# UI.net
KiCad netlist of a schematic drawn in Altium Designer
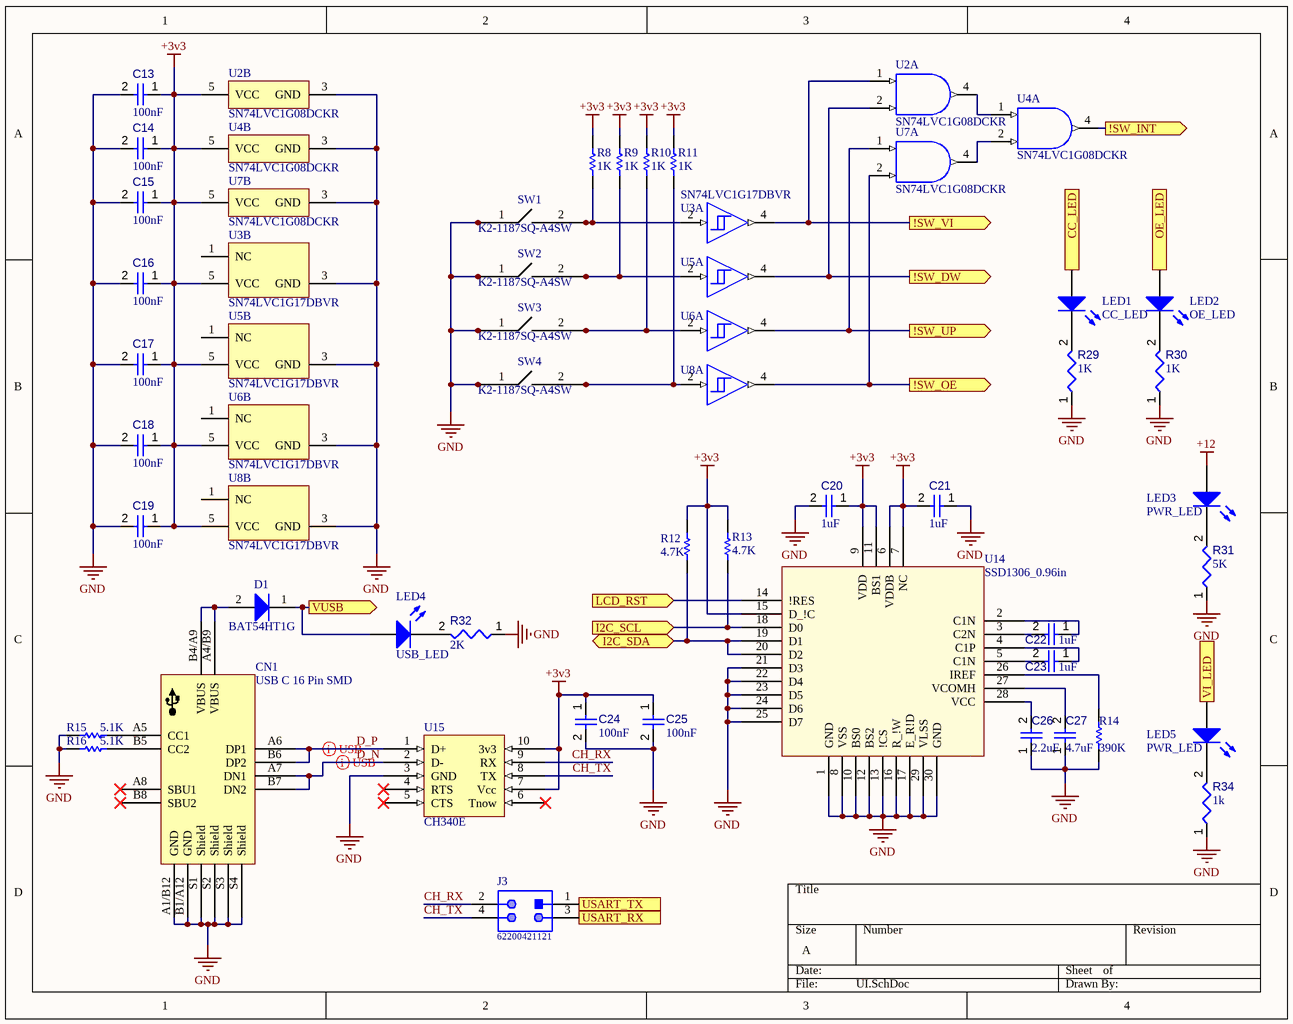
[diagram p0: UI.SchDoc]

(export (version "E")
  (design (tool "Eeschema 10.0.6"))
  (components
    (comp (ref "C13")
      (value "100nF")
      (footprint "CAPC2013X95X50ML10T25")
      (description "Chip Capacitor, 100 nF, +/- 10%, 50 V, 0805 (2012 Metric)")
      (fields (field (name "TOLERANCE") "10%") (field (name "Comment") "Capacitor 100 nF +/-10% 50 V 0805"))
      (libsource (lib "Aditya Sehgal") (part "CAP-NP-2"))
    )
    (comp (ref "C14")
      (value "100nF")
      (footprint "CAPC2013X95X50ML10T25")
      (description "Chip Capacitor, 100 nF, +/- 10%, 50 V, 0805 (2012 Metric)")
      (fields (field (name "TOLERANCE") "10%") (field (name "Comment") "Capacitor 100 nF +/-10% 50 V 0805"))
      (libsource (lib "Aditya Sehgal") (part "CAP-NP-2"))
    )
    (comp (ref "C15")
      (value "100nF")
      (footprint "CAPC2013X95X50ML10T25")
      (description "Chip Capacitor, 100 nF, +/- 10%, 50 V, 0805 (2012 Metric)")
      (fields (field (name "TOLERANCE") "10%") (field (name "Comment") "Capacitor 100 nF +/-10% 50 V 0805"))
      (libsource (lib "Aditya Sehgal") (part "CAP-NP-2"))
    )
    (comp (ref "C16")
      (value "100nF")
      (footprint "CAPC2013X95X50ML10T25")
      (description "Chip Capacitor, 100 nF, +/- 10%, 50 V, 0805 (2012 Metric)")
      (fields (field (name "TOLERANCE") "10%") (field (name "Comment") "Capacitor 100 nF +/-10% 50 V 0805"))
      (libsource (lib "Aditya Sehgal") (part "CAP-NP-2"))
    )
    (comp (ref "C17")
      (value "100nF")
      (footprint "CAPC2013X95X50ML10T25")
      (description "Chip Capacitor, 100 nF, +/- 10%, 50 V, 0805 (2012 Metric)")
      (fields (field (name "TOLERANCE") "10%") (field (name "Comment") "Capacitor 100 nF +/-10% 50 V 0805"))
      (libsource (lib "Aditya Sehgal") (part "CAP-NP-2"))
    )
    (comp (ref "C18")
      (value "100nF")
      (footprint "CAPC2013X95X50ML10T25")
      (description "Chip Capacitor, 100 nF, +/- 10%, 50 V, 0805 (2012 Metric)")
      (fields (field (name "TOLERANCE") "10%") (field (name "Comment") "Capacitor 100 nF +/-10% 50 V 0805"))
      (libsource (lib "Aditya Sehgal") (part "CAP-NP-2"))
    )
    (comp (ref "C19")
      (value "100nF")
      (footprint "CAPC2013X95X50ML10T25")
      (description "Chip Capacitor, 100 nF, +/- 10%, 50 V, 0805 (2012 Metric)")
      (fields (field (name "TOLERANCE") "10%") (field (name "Comment") "Capacitor 100 nF +/-10% 50 V 0805"))
      (libsource (lib "Aditya Sehgal") (part "CAP-NP-2"))
    )
    (comp (ref "C20")
      (value "1uF")
      (footprint "CAPC2013X95X50ML10T25")
      (description "Chip Capacitor, 100 nF, +/- 10%, 50 V, 0805 (2012 Metric)")
      (fields (field (name "TOLERANCE") "10%") (field (name "Comment") "Capacitor 100 nF +/-10% 50 V 0805"))
      (libsource (lib "Aditya Sehgal") (part "CAP-NP-2"))
    )
    (comp (ref "C21")
      (value "1uF")
      (footprint "CAPC2013X95X50ML10T25")
      (description "Chip Capacitor, 100 nF, +/- 10%, 50 V, 0805 (2012 Metric)")
      (fields (field (name "TOLERANCE") "10%") (field (name "Comment") "Capacitor 100 nF +/-10% 50 V 0805"))
      (libsource (lib "Aditya Sehgal") (part "CAP-NP-2"))
    )
    (comp (ref "C22")
      (value "1uF")
      (footprint "CAPC2013X95X50ML10T25")
      (description "Chip Capacitor, 100 nF, +/- 10%, 50 V, 0805 (2012 Metric)")
      (fields (field (name "TOLERANCE") "10%") (field (name "Comment") "Capacitor 100 nF +/-10% 50 V 0805"))
      (libsource (lib "Aditya Sehgal") (part "CAP-NP-2"))
    )
    (comp (ref "C23")
      (value "1uF")
      (footprint "CAPC2013X95X50ML10T25")
      (description "Chip Capacitor, 100 nF, +/- 10%, 50 V, 0805 (2012 Metric)")
      (fields (field (name "TOLERANCE") "10%") (field (name "Comment") "Capacitor 100 nF +/-10% 50 V 0805"))
      (libsource (lib "Aditya Sehgal") (part "CAP-NP-2"))
    )
    (comp (ref "C24")
      (value "100nF")
      (footprint "CAPC2013X95X50ML10T25")
      (description "Chip Capacitor, 100 nF, +/- 10%, 50 V, 0805 (2012 Metric)")
      (fields (field (name "TOLERANCE") "10%") (field (name "Comment") "Capacitor 100 nF +/-10% 50 V 0805"))
      (libsource (lib "Aditya Sehgal") (part "CAP-NP-2"))
    )
    (comp (ref "C25")
      (value "100nF")
      (footprint "CAPC2013X95X50ML10T25")
      (description "Chip Capacitor, 100 nF, +/- 10%, 50 V, 0805 (2012 Metric)")
      (fields (field (name "TOLERANCE") "10%") (field (name "Comment") "Capacitor 100 nF +/-10% 50 V 0805"))
      (libsource (lib "Aditya Sehgal") (part "CAP-NP-2"))
    )
    (comp (ref "C26")
      (value "2.2uF")
      (footprint "CAPC2013X95X50ML10T25")
      (description "Chip Capacitor, 100 nF, +/- 10%, 50 V, 0805 (2012 Metric)")
      (fields (field (name "TOLERANCE") "10%") (field (name "Comment") "Capacitor 100 nF +/-10% 50 V 0805"))
      (libsource (lib "Aditya Sehgal") (part "CAP-NP-2"))
    )
    (comp (ref "C27")
      (value "4.7uF")
      (footprint "CAPC2013X95X50ML10T25")
      (description "Chip Capacitor, 100 nF, +/- 10%, 50 V, 0805 (2012 Metric)")
      (fields (field (name "TOLERANCE") "10%") (field (name "Comment") "Capacitor 100 nF +/-10% 50 V 0805"))
      (libsource (lib "Aditya Sehgal") (part "CAP-NP-2"))
    )
    (comp (ref "CN1")
      (value "USB C 16 Pin SMD")
      (footprint "USB C 16 Pin SMD-Footprint-1")
      (description "C167321 Jing Extension")
      (libsource (lib "Aditya Sehgal") (part "USB C 16 Pin SMD"))
    )
    (comp (ref "D1")
      (value "BAT54HT1G")
      (footprint "ONSC-SOD-323-2-477-02_V")
      (description "Schottky Barrier Diode, 2-Pin SOD-323, Pb-Free, Tape and Reel")
      (fields (field (name "MANUFACTURER") "On Semiconductor"))
      (libsource (lib "Altium Content Vault") (part "ONSC-D-K1A2-2"))
    )
    (comp (ref "J3")
      (value "62200421121")
      (footprint "62200421121")
      (description "THT Vertical Pin Header WR-PHD, Pitch 1.27 mm, Dual Row, 4 pins")
      (fields (field (name "MANUFACTURER") "Wurth Elektronik") (field (name "PUBLISHER") "WurthElektronik"))
      (libsource (lib "Altium Content Vault") (part "WE-CN-2P-M-R4"))
    )
    (comp (ref "LED1")
      (value "CC_LED")
      (footprint "0805_A")
      (description "SMD mono-color Chip LED, WL-SMCW, Super Red")
      (fields (field (name "MANUFACTURER") "Wuerth Elektronik") (field (name "PARTNUMBER") "150080SS75000"))
      (libsource (lib "Altium Content Vault") (part "WE-LED_K1A2-2"))
    )
    (comp (ref "LED2")
      (value "OE_LED")
      (footprint "0805_A")
      (description "SMD mono-color Chip LED, WL-SMCW, Super Red")
      (fields (field (name "MANUFACTURER") "Wuerth Elektronik") (field (name "PARTNUMBER") "150080SS75000"))
      (libsource (lib "Altium Content Vault") (part "WE-LED_K1A2-2"))
    )
    (comp (ref "LED3")
      (value "PWR_LED")
      (footprint "0805_A")
      (description "SMD mono-color Chip LED, WL-SMCW, Super Red")
      (fields (field (name "MANUFACTURER") "Wuerth Elektronik") (field (name "PARTNUMBER") "150080SS75000"))
      (libsource (lib "Altium Content Vault") (part "WE-LED_K1A2-2"))
    )
    (comp (ref "LED4")
      (value "USB_LED")
      (footprint "0805_A")
      (description "SMD mono-color Chip LED, WL-SMCW, Super Red")
      (fields (field (name "MANUFACTURER") "Wuerth Elektronik") (field (name "PARTNUMBER") "150080SS75000"))
      (libsource (lib "Altium Content Vault") (part "WE-LED_K1A2-2"))
    )
    (comp (ref "LED5")
      (value "PWR_LED")
      (footprint "0805_A")
      (description "SMD mono-color Chip LED, WL-SMCW, Super Red")
      (fields (field (name "MANUFACTURER") "Wuerth Elektronik") (field (name "PARTNUMBER") "150080SS75000"))
      (libsource (lib "Altium Content Vault") (part "WE-LED_K1A2-2"))
    )
    (comp (ref "R8")
      (value "1K")
      (footprint "RESC2013X50X35ML15T15")
      (description "Chip Resistor, 0 Ohm, +/- 1%, 125 mW, -55 to 155 degC, 0805 (2012 Metric)")
      (fields (field (name "TOLERANCE") "1%") (field (name "POWER") "125mW"))
      (libsource (lib "Aditya Sehgal") (part "RES-2"))
    )
    (comp (ref "R9")
      (value "1K")
      (footprint "RESC2013X50X35ML15T15")
      (description "Chip Resistor, 0 Ohm, +/- 1%, 125 mW, -55 to 155 degC, 0805 (2012 Metric)")
      (fields (field (name "TOLERANCE") "1%") (field (name "POWER") "125mW"))
      (libsource (lib "Aditya Sehgal") (part "RES-2"))
    )
    (comp (ref "R10")
      (value "1K")
      (footprint "RESC2013X50X35ML15T15")
      (description "Chip Resistor, 0 Ohm, +/- 1%, 125 mW, -55 to 155 degC, 0805 (2012 Metric)")
      (fields (field (name "TOLERANCE") "1%") (field (name "POWER") "125mW"))
      (libsource (lib "Aditya Sehgal") (part "RES-2"))
    )
    (comp (ref "R11")
      (value "1K")
      (footprint "RESC2013X50X35ML15T15")
      (description "Chip Resistor, 0 Ohm, +/- 1%, 125 mW, -55 to 155 degC, 0805 (2012 Metric)")
      (fields (field (name "TOLERANCE") "1%") (field (name "POWER") "125mW"))
      (libsource (lib "Aditya Sehgal") (part "RES-2"))
    )
    (comp (ref "R12")
      (value "4.7K")
      (footprint "RESC2013X50X35ML15T15")
      (description "Chip Resistor, 0 Ohm, +/- 1%, 125 mW, -55 to 155 degC, 0805 (2012 Metric)")
      (fields (field (name "TOLERANCE") "1%") (field (name "POWER") "125mW"))
      (libsource (lib "Aditya Sehgal") (part "RES-2"))
    )
    (comp (ref "R13")
      (value "4.7K")
      (footprint "RESC2013X50X35ML15T15")
      (description "Chip Resistor, 0 Ohm, +/- 1%, 125 mW, -55 to 155 degC, 0805 (2012 Metric)")
      (fields (field (name "TOLERANCE") "1%") (field (name "POWER") "125mW"))
      (libsource (lib "Aditya Sehgal") (part "RES-2"))
    )
    (comp (ref "R14")
      (value "390K")
      (footprint "RESC2013X50X35ML15T15")
      (description "Chip Resistor, 0 Ohm, +/- 1%, 125 mW, -55 to 155 degC, 0805 (2012 Metric)")
      (fields (field (name "TOLERANCE") "1%") (field (name "POWER") "125mW"))
      (libsource (lib "Aditya Sehgal") (part "RES-2"))
    )
    (comp (ref "R15")
      (value "5.1K")
      (footprint "RESC2013X50X35ML15T15")
      (description "Chip Resistor, 0 Ohm, +/- 1%, 125 mW, -55 to 155 degC, 0805 (2012 Metric)")
      (fields (field (name "TOLERANCE") "1%") (field (name "POWER") "125mW"))
      (libsource (lib "Aditya Sehgal") (part "RES-2"))
    )
    (comp (ref "R16")
      (value "5.1K")
      (footprint "RESC2013X50X35ML15T15")
      (description "Chip Resistor, 0 Ohm, +/- 1%, 125 mW, -55 to 155 degC, 0805 (2012 Metric)")
      (fields (field (name "TOLERANCE") "1%") (field (name "POWER") "125mW"))
      (libsource (lib "Aditya Sehgal") (part "RES-2"))
    )
    (comp (ref "R29")
      (value "1K")
      (footprint "RESC0805(2012)_L")
      (description "Chip Resistor, 470 Ohms, +/-5%, 125 mW, -55 to 155 degC, 0805")
      (fields (field (name "POWER") "125mW") (field (name "TOLERANCE") "5%"))
      (libsource (lib "University of California Santa Cruz") (part "RES-2"))
    )
    (comp (ref "R30")
      (value "1K")
      (footprint "RESC0805(2012)_L")
      (description "Chip Resistor, 470 Ohms, +/-5%, 125 mW, -55 to 155 degC, 0805")
      (fields (field (name "POWER") "125mW") (field (name "TOLERANCE") "5%"))
      (libsource (lib "University of California Santa Cruz") (part "RES-2"))
    )
    (comp (ref "R31")
      (value "5K")
      (footprint "RESC0805(2012)_L")
      (description "Chip Resistor, 470 Ohms, +/-5%, 125 mW, -55 to 155 degC, 0805")
      (fields (field (name "POWER") "125mW") (field (name "TOLERANCE") "5%"))
      (libsource (lib "University of California Santa Cruz") (part "RES-2"))
    )
    (comp (ref "R32")
      (value "2K")
      (footprint "RESC0805(2012)_L")
      (description "Chip Resistor, 470 Ohms, +/-5%, 125 mW, -55 to 155 degC, 0805")
      (fields (field (name "POWER") "125mW") (field (name "TOLERANCE") "5%"))
      (libsource (lib "University of California Santa Cruz") (part "RES-2"))
    )
    (comp (ref "R34")
      (value "1k")
      (footprint "RESC0805(2012)_L")
      (description "Chip Resistor, 470 Ohms, +/-5%, 125 mW, -55 to 155 degC, 0805")
      (fields (field (name "POWER") "125mW") (field (name "TOLERANCE") "5%"))
      (libsource (lib "University of California Santa Cruz") (part "RES-2"))
    )
    (comp (ref "SW1")
      (value "K2-1187SQ-A4SW")
      (footprint "K2-1187SQ-A4SW-Footprint-1")
      (description "4 pin SMD switch")
      (libsource (lib "Aditya Sehgal") (part "K2-1187SQ-A4SW"))
    )
    (comp (ref "SW2")
      (value "K2-1187SQ-A4SW")
      (footprint "K2-1187SQ-A4SW-Footprint-1")
      (description "4 pin SMD switch")
      (libsource (lib "Aditya Sehgal") (part "K2-1187SQ-A4SW"))
    )
    (comp (ref "SW3")
      (value "K2-1187SQ-A4SW")
      (footprint "K2-1187SQ-A4SW-Footprint-1")
      (description "4 pin SMD switch")
      (libsource (lib "Aditya Sehgal") (part "K2-1187SQ-A4SW"))
    )
    (comp (ref "SW4")
      (value "K2-1187SQ-A4SW")
      (footprint "K2-1187SQ-A4SW-Footprint-1")
      (description "4 pin SMD switch")
      (libsource (lib "Aditya Sehgal") (part "K2-1187SQ-A4SW"))
    )
    (comp (ref "U2")
      (value "SN74LVC1G08DCKR")
      (footprint "DCK0005A_M")
      (description "Single 2-Input Positive-AND Gate, DCK0005A, LARGE T&R")
      (fields
        (field (name "GENERIC PART NUMBER") "SN74LVC1G08")
        (field (name "MANUFACTURER") "Texas Instruments")
      )
      (libsource (lib "Altium Content Vault") (part "TI-SN74XXX1X08-5"))
    )
    (comp (ref "U3")
      (value "SN74LVC1G17DBVR")
      (footprint "DBV0005A_L")
      (description "Single Schmitt-Trigger Buffer, DBV0005A, LARGE T&R")
      (fields
        (field (name "MANUFACTURER") "Texas Instruments")
        (field (name "GENERIC PART NUMBER") "SN74LVC1G17")
      )
      (libsource (lib "Altium Content Vault") (part "TI-SN74XXX1XXX-XX-5-SCHMITT"))
    )
    (comp (ref "U4")
      (value "SN74LVC1G08DCKR")
      (footprint "DCK0005A_M")
      (description "Single 2-Input Positive-AND Gate, DCK0005A, LARGE T&R")
      (fields
        (field (name "GENERIC PART NUMBER") "SN74LVC1G08")
        (field (name "MANUFACTURER") "Texas Instruments")
      )
      (libsource (lib "Altium Content Vault") (part "TI-SN74XXX1X08-5"))
    )
    (comp (ref "U5")
      (value "SN74LVC1G17DBVR")
      (footprint "DBV0005A_L")
      (description "Single Schmitt-Trigger Buffer, DBV0005A, LARGE T&R")
      (fields
        (field (name "MANUFACTURER") "Texas Instruments")
        (field (name "GENERIC PART NUMBER") "SN74LVC1G17")
      )
      (libsource (lib "Altium Content Vault") (part "TI-SN74XXX1XXX-XX-5-SCHMITT"))
    )
    (comp (ref "U6")
      (value "SN74LVC1G17DBVR")
      (footprint "DBV0005A_L")
      (description "Single Schmitt-Trigger Buffer, DBV0005A, LARGE T&R")
      (fields
        (field (name "MANUFACTURER") "Texas Instruments")
        (field (name "GENERIC PART NUMBER") "SN74LVC1G17")
      )
      (libsource (lib "Altium Content Vault") (part "TI-SN74XXX1XXX-XX-5-SCHMITT"))
    )
    (comp (ref "U7")
      (value "SN74LVC1G08DCKR")
      (footprint "DCK0005A_M")
      (description "Single 2-Input Positive-AND Gate, DCK0005A, LARGE T&R")
      (fields
        (field (name "GENERIC PART NUMBER") "SN74LVC1G08")
        (field (name "MANUFACTURER") "Texas Instruments")
      )
      (libsource (lib "Altium Content Vault") (part "TI-SN74XXX1X08-5"))
    )
    (comp (ref "U8")
      (value "SN74LVC1G17DBVR")
      (footprint "DBV0005A_L")
      (description "Single Schmitt-Trigger Buffer, DBV0005A, LARGE T&R")
      (fields
        (field (name "MANUFACTURER") "Texas Instruments")
        (field (name "GENERIC PART NUMBER") "SN74LVC1G17")
      )
      (libsource (lib "Altium Content Vault") (part "TI-SN74XXX1XXX-XX-5-SCHMITT"))
    )
    (comp (ref "U14")
      (value "SSD1306_0.96in")
      (footprint "SSD1306_0.96in-Footprint-1")
      (description "C91755")
      (libsource (lib "Aditya Sehgal") (part "SSD1306_0.96in"))
    )
    (comp (ref "U15")
      (value "CH340E")
      (footprint "TSSOP50P490X110-10N")
      (description "USB to UART Converter")
      (libsource (lib "Aditya Sehgal") (part "CH340E"))
    )
  )
  (nets
    (net (code "1") (name "+3v3") (class "Default")
      (node (ref "C13") (pin "1") (pinfunction "1_1") (pintype "passive"))
      (node (ref "C14") (pin "1") (pinfunction "1_1") (pintype "passive"))
      (node (ref "C15") (pin "1") (pinfunction "1_1") (pintype "passive"))
      (node (ref "C16") (pin "1") (pinfunction "1_1") (pintype "passive"))
      (node (ref "C17") (pin "1") (pinfunction "1_1") (pintype "passive"))
      (node (ref "C18") (pin "1") (pinfunction "1_1") (pintype "passive"))
      (node (ref "C19") (pin "1") (pinfunction "1_1") (pintype "passive"))
      (node (ref "C20") (pin "1") (pinfunction "1_1") (pintype "passive"))
      (node (ref "C21") (pin "2") (pinfunction "2_2") (pintype "passive"))
      (node (ref "C24") (pin "1") (pinfunction "1_1") (pintype "passive"))
      (node (ref "C25") (pin "1") (pinfunction "1_1") (pintype "passive"))
      (node (ref "R10") (pin "2") (pinfunction "2_2") (pintype "passive"))
      (node (ref "R11") (pin "2") (pinfunction "2_2") (pintype "passive"))
      (node (ref "R12") (pin "2") (pinfunction "2_2") (pintype "passive"))
      (node (ref "R13") (pin "2") (pinfunction "2_2") (pintype "passive"))
      (node (ref "R8") (pin "2") (pinfunction "2_2") (pintype "passive"))
      (node (ref "R9") (pin "2") (pinfunction "2_2") (pintype "passive"))
      (node (ref "U14") (pin "11") (pinfunction "BS1_11") (pintype "passive"))
      (node (ref "U14") (pin "15") (pinfunction "D_!C_15") (pintype "passive"))
      (node (ref "U14") (pin "6") (pinfunction "VDDB_6") (pintype "passive"))
      (node (ref "U14") (pin "7") (pinfunction "NC_7") (pintype "passive"))
      (node (ref "U14") (pin "9") (pinfunction "VDD_9") (pintype "passive"))
      (node (ref "U15") (pin "10") (pinfunction "3v3_10") (pintype "input"))
      (node (ref "U15") (pin "7") (pinfunction "Vcc_7") (pintype "input"))
      (node (ref "U2") (pin "5") (pinfunction "VCC_5") (pintype "power_in"))
      (node (ref "U3") (pin "5") (pinfunction "VCC_5") (pintype "power_in"))
      (node (ref "U4") (pin "5") (pinfunction "VCC_5") (pintype "power_in"))
      (node (ref "U5") (pin "5") (pinfunction "VCC_5") (pintype "power_in"))
      (node (ref "U6") (pin "5") (pinfunction "VCC_5") (pintype "power_in"))
      (node (ref "U7") (pin "5") (pinfunction "VCC_5") (pintype "power_in"))
      (node (ref "U8") (pin "5") (pinfunction "VCC_5") (pintype "power_in"))
    )
    (net (code "2") (name "+12") (class "Default")
      (node (ref "LED3") (pin "2") (pinfunction "A_2") (pintype "passive"))
    )
    (net (code "3") (name "/!SW_DW") (class "Default")
      (node (ref "U2") (pin "2") (pinfunction "B_2") (pintype "input"))
      (node (ref "U5") (pin "4") (pinfunction "Y_4") (pintype "output"))
    )
    (net (code "4") (name "/!SW_INT") (class "Default")
      (node (ref "U4") (pin "4") (pinfunction "Y_4") (pintype "output"))
    )
    (net (code "5") (name "/!SW_OE") (class "Default")
      (node (ref "U7") (pin "2") (pinfunction "B_2") (pintype "input"))
      (node (ref "U8") (pin "4") (pinfunction "Y_4") (pintype "output"))
    )
    (net (code "6") (name "/!SW_UP") (class "Default")
      (node (ref "U6") (pin "4") (pinfunction "Y_4") (pintype "output"))
      (node (ref "U7") (pin "1") (pinfunction "A_1") (pintype "input"))
    )
    (net (code "7") (name "/!SW_VI") (class "Default")
      (node (ref "U2") (pin "1") (pinfunction "A_1") (pintype "input"))
      (node (ref "U3") (pin "4") (pinfunction "Y_4") (pintype "output"))
    )
    (net (code "8") (name "/CC_LED") (class "Default")
      (node (ref "LED1") (pin "2") (pinfunction "A_2") (pintype "passive"))
    )
    (net (code "9") (name "/CH_RX") (class "Default")
      (node (ref "J3") (pin "2") (pinfunction "2_2") (pintype "passive"))
      (node (ref "U15") (pin "9") (pinfunction "RX_9") (pintype "input"))
    )
    (net (code "10") (name "/CH_TX") (class "Default")
      (node (ref "J3") (pin "4") (pinfunction "4_4") (pintype "passive"))
      (node (ref "U15") (pin "8") (pinfunction "TX_8") (pintype "input"))
    )
    (net (code "11") (name "/D_N") (class "Default")
      (node (ref "CN1") (pin "A7") (pinfunction "DN1_A7") (pintype "passive"))
      (node (ref "CN1") (pin "B7") (pinfunction "DN2_B7") (pintype "passive"))
      (node (ref "U15") (pin "2") (pinfunction "D-_2") (pintype "input"))
    )
    (net (code "12") (name "/D_P") (class "Default")
      (node (ref "CN1") (pin "A6") (pinfunction "DP1_A6") (pintype "passive"))
      (node (ref "CN1") (pin "B6") (pinfunction "DP2_B6") (pintype "passive"))
      (node (ref "U15") (pin "1") (pinfunction "D+_1") (pintype "input"))
    )
    (net (code "13") (name "/I2C_SCL") (class "Default")
      (node (ref "R13") (pin "1") (pinfunction "1_1") (pintype "passive"))
      (node (ref "U14") (pin "18") (pinfunction "D0_18") (pintype "passive"))
    )
    (net (code "14") (name "/I2C_SDA") (class "Default")
      (node (ref "R12") (pin "1") (pinfunction "1_1") (pintype "passive"))
      (node (ref "U14") (pin "19") (pinfunction "D1_19") (pintype "passive"))
      (node (ref "U14") (pin "20") (pinfunction "D2_20") (pintype "passive"))
    )
    (net (code "15") (name "/LCD_RST") (class "Default")
      (node (ref "U14") (pin "14") (pinfunction "!RES_14") (pintype "passive"))
    )
    (net (code "16") (name "/OE_LED") (class "Default")
      (node (ref "LED2") (pin "2") (pinfunction "A_2") (pintype "passive"))
    )
    (net (code "17") (name "/USART_RX") (class "Default")
      (node (ref "J3") (pin "3") (pinfunction "3_3") (pintype "passive"))
    )
    (net (code "18") (name "/USART_TX") (class "Default")
      (node (ref "J3") (pin "1") (pinfunction "1_1") (pintype "passive"))
    )
    (net (code "19") (name "/VI_LED") (class "Default")
      (node (ref "LED5") (pin "2") (pinfunction "A_2") (pintype "passive"))
    )
    (net (code "20") (name "/VUSB") (class "Default")
      (node (ref "D1") (pin "1") (pinfunction "K_1") (pintype "passive"))
      (node (ref "LED4") (pin "2") (pinfunction "A_2") (pintype "passive"))
    )
    (net (code "21") (name "GND") (class "Default")
      (node (ref "C13") (pin "2") (pinfunction "2_2") (pintype "passive"))
      (node (ref "C14") (pin "2") (pinfunction "2_2") (pintype "passive"))
      (node (ref "C15") (pin "2") (pinfunction "2_2") (pintype "passive"))
      (node (ref "C16") (pin "2") (pinfunction "2_2") (pintype "passive"))
      (node (ref "C17") (pin "2") (pinfunction "2_2") (pintype "passive"))
      (node (ref "C18") (pin "2") (pinfunction "2_2") (pintype "passive"))
      (node (ref "C19") (pin "2") (pinfunction "2_2") (pintype "passive"))
      (node (ref "C20") (pin "2") (pinfunction "2_2") (pintype "passive"))
      (node (ref "C21") (pin "1") (pinfunction "1_1") (pintype "passive"))
      (node (ref "C24") (pin "2") (pinfunction "2_2") (pintype "passive"))
      (node (ref "C25") (pin "2") (pinfunction "2_2") (pintype "passive"))
      (node (ref "C26") (pin "1") (pinfunction "1_1") (pintype "passive"))
      (node (ref "C27") (pin "1") (pinfunction "1_1") (pintype "passive"))
      (node (ref "CN1") (pin "A1/B12") (pinfunction "GND_A1/B12") (pintype "power_in"))
      (node (ref "CN1") (pin "B1/A12") (pinfunction "GND_B1/A12") (pintype "power_in"))
      (node (ref "CN1") (pin "S1") (pinfunction "Shield_S1") (pintype "power_in"))
      (node (ref "CN1") (pin "S2") (pinfunction "Shield_S2") (pintype "power_in"))
      (node (ref "CN1") (pin "S3") (pinfunction "Shield_S3") (pintype "power_in"))
      (node (ref "CN1") (pin "S4") (pinfunction "Shield_S4") (pintype "power_in"))
      (node (ref "R14") (pin "2") (pinfunction "2_2") (pintype "passive"))
      (node (ref "R15") (pin "2") (pinfunction "2_2") (pintype "passive"))
      (node (ref "R16") (pin "2") (pinfunction "2_2") (pintype "passive"))
      (node (ref "R29") (pin "1") (pinfunction "1_1") (pintype "passive"))
      (node (ref "R30") (pin "1") (pinfunction "1_1") (pintype "passive"))
      (node (ref "R31") (pin "1") (pinfunction "1_1") (pintype "passive"))
      (node (ref "R32") (pin "1") (pinfunction "1_1") (pintype "passive"))
      (node (ref "R34") (pin "1") (pinfunction "1_1") (pintype "passive"))
      (node (ref "SW1") (pin "1") (pinfunction "1_1") (pintype "passive"))
      (node (ref "SW1") (pin "3") (pinfunction "3_3") (pintype "passive"))
      (node (ref "SW2") (pin "1") (pinfunction "1_1") (pintype "passive"))
      (node (ref "SW2") (pin "3") (pinfunction "3_3") (pintype "passive"))
      (node (ref "SW3") (pin "1") (pinfunction "1_1") (pintype "passive"))
      (node (ref "SW3") (pin "3") (pinfunction "3_3") (pintype "passive"))
      (node (ref "SW4") (pin "1") (pinfunction "1_1") (pintype "passive"))
      (node (ref "SW4") (pin "3") (pinfunction "3_3") (pintype "passive"))
      (node (ref "U14") (pin "1") (pinfunction "GND_1") (pintype "passive"))
      (node (ref "U14") (pin "10") (pinfunction "BS0_10") (pintype "passive"))
      (node (ref "U14") (pin "12") (pinfunction "BS2_12") (pintype "passive"))
      (node (ref "U14") (pin "13") (pinfunction "!CS_13") (pintype "passive"))
      (node (ref "U14") (pin "16") (pinfunction "R_!W_16") (pintype "passive"))
      (node (ref "U14") (pin "17") (pinfunction "E_R!D_17") (pintype "passive"))
      (node (ref "U14") (pin "21") (pinfunction "D3_21") (pintype "passive"))
      (node (ref "U14") (pin "22") (pinfunction "D4_22") (pintype "passive"))
      (node (ref "U14") (pin "23") (pinfunction "D5_23") (pintype "passive"))
      (node (ref "U14") (pin "24") (pinfunction "D6_24") (pintype "passive"))
      (node (ref "U14") (pin "25") (pinfunction "D7_25") (pintype "passive"))
      (node (ref "U14") (pin "29") (pinfunction "VLSS_29") (pintype "passive"))
      (node (ref "U14") (pin "30") (pinfunction "GND_30") (pintype "passive"))
      (node (ref "U14") (pin "8") (pinfunction "VSS_8") (pintype "passive"))
      (node (ref "U15") (pin "3") (pinfunction "GND_3") (pintype "input"))
      (node (ref "U2") (pin "3") (pinfunction "GND_3") (pintype "power_in"))
      (node (ref "U3") (pin "3") (pinfunction "GND_3") (pintype "power_in"))
      (node (ref "U4") (pin "3") (pinfunction "GND_3") (pintype "power_in"))
      (node (ref "U5") (pin "3") (pinfunction "GND_3") (pintype "power_in"))
      (node (ref "U6") (pin "3") (pinfunction "GND_3") (pintype "power_in"))
      (node (ref "U7") (pin "3") (pinfunction "GND_3") (pintype "power_in"))
      (node (ref "U8") (pin "3") (pinfunction "GND_3") (pintype "power_in"))
    )
    (net (code "22") (name "Net-(C22-Pad1)") (class "Default")
      (node (ref "C22") (pin "1") (pinfunction "1_1") (pintype "passive"))
      (node (ref "U14") (pin "2") (pinfunction "C1N_2") (pintype "passive"))
    )
    (net (code "23") (name "Net-(C23-Pad2)") (class "Default")
      (node (ref "C23") (pin "2") (pinfunction "2_2") (pintype "passive"))
      (node (ref "U14") (pin "5") (pinfunction "C1N_5") (pintype "passive"))
    )
    (net (code "24") (name "Net-(CN1-CC1)") (class "Default")
      (node (ref "CN1") (pin "A5") (pinfunction "CC1_A5") (pintype "passive"))
      (node (ref "R15") (pin "1") (pinfunction "1_1") (pintype "passive"))
    )
    (net (code "25") (name "Net-(CN1-CC2)") (class "Default")
      (node (ref "CN1") (pin "B5") (pinfunction "CC2_B5") (pintype "passive"))
      (node (ref "R16") (pin "1") (pinfunction "1_1") (pintype "passive"))
    )
    (net (code "26") (name "Net-(D1-A)") (class "Default")
      (node (ref "CN1") (pin "A4/B9") (pinfunction "VBUS_A4/B9") (pintype "power_in"))
      (node (ref "CN1") (pin "B4/A9") (pinfunction "VBUS_B4/A9") (pintype "power_in"))
      (node (ref "D1") (pin "2") (pinfunction "A_2") (pintype "passive"))
    )
    (net (code "27") (name "Net-(LED1-K)") (class "Default")
      (node (ref "LED1") (pin "1") (pinfunction "K_1") (pintype "passive"))
      (node (ref "R29") (pin "2") (pinfunction "2_2") (pintype "passive"))
    )
    (net (code "28") (name "Net-(LED2-K)") (class "Default")
      (node (ref "LED2") (pin "1") (pinfunction "K_1") (pintype "passive"))
      (node (ref "R30") (pin "2") (pinfunction "2_2") (pintype "passive"))
    )
    (net (code "29") (name "Net-(LED3-K)") (class "Default")
      (node (ref "LED3") (pin "1") (pinfunction "K_1") (pintype "passive"))
      (node (ref "R31") (pin "2") (pinfunction "2_2") (pintype "passive"))
    )
    (net (code "30") (name "Net-(LED4-K)") (class "Default")
      (node (ref "LED4") (pin "1") (pinfunction "K_1") (pintype "passive"))
      (node (ref "R32") (pin "2") (pinfunction "2_2") (pintype "passive"))
    )
    (net (code "31") (name "Net-(LED5-K)") (class "Default")
      (node (ref "LED5") (pin "1") (pinfunction "K_1") (pintype "passive"))
      (node (ref "R34") (pin "2") (pinfunction "2_2") (pintype "passive"))
    )
    (net (code "32") (name "Net-(U2A-Y)") (class "Default")
      (node (ref "U2") (pin "4") (pinfunction "Y_4") (pintype "output"))
      (node (ref "U4") (pin "1") (pinfunction "A_1") (pintype "input"))
    )
    (net (code "33") (name "Net-(U3A-A)") (class "Default")
      (node (ref "R8") (pin "1") (pinfunction "1_1") (pintype "passive"))
      (node (ref "SW1") (pin "2") (pinfunction "2_2") (pintype "passive"))
      (node (ref "SW1") (pin "4") (pinfunction "4_4") (pintype "passive"))
      (node (ref "U3") (pin "2") (pinfunction "A_2") (pintype "input"))
    )
    (net (code "34") (name "Net-(U4A-B)") (class "Default")
      (node (ref "U4") (pin "2") (pinfunction "B_2") (pintype "input"))
      (node (ref "U7") (pin "4") (pinfunction "Y_4") (pintype "output"))
    )
    (net (code "35") (name "Net-(U5A-A)") (class "Default")
      (node (ref "R9") (pin "1") (pinfunction "1_1") (pintype "passive"))
      (node (ref "SW2") (pin "2") (pinfunction "2_2") (pintype "passive"))
      (node (ref "SW2") (pin "4") (pinfunction "4_4") (pintype "passive"))
      (node (ref "U5") (pin "2") (pinfunction "A_2") (pintype "input"))
    )
    (net (code "36") (name "Net-(U6A-A)") (class "Default")
      (node (ref "R10") (pin "1") (pinfunction "1_1") (pintype "passive"))
      (node (ref "SW3") (pin "2") (pinfunction "2_2") (pintype "passive"))
      (node (ref "SW3") (pin "4") (pinfunction "4_4") (pintype "passive"))
      (node (ref "U6") (pin "2") (pinfunction "A_2") (pintype "input"))
    )
    (net (code "37") (name "Net-(U8A-A)") (class "Default")
      (node (ref "R11") (pin "1") (pinfunction "1_1") (pintype "passive"))
      (node (ref "SW4") (pin "2") (pinfunction "2_2") (pintype "passive"))
      (node (ref "SW4") (pin "4") (pinfunction "4_4") (pintype "passive"))
      (node (ref "U8") (pin "2") (pinfunction "A_2") (pintype "input"))
    )
    (net (code "38") (name "Net-(U14-C1P)") (class "Default")
      (node (ref "C23") (pin "1") (pinfunction "1_1") (pintype "passive"))
      (node (ref "U14") (pin "4") (pinfunction "C1P_4") (pintype "passive"))
    )
    (net (code "39") (name "Net-(U14-C2N)") (class "Default")
      (node (ref "C22") (pin "2") (pinfunction "2_2") (pintype "passive"))
      (node (ref "U14") (pin "3") (pinfunction "C2N_3") (pintype "passive"))
    )
    (net (code "40") (name "Net-(U14-IREF)") (class "Default")
      (node (ref "R14") (pin "1") (pinfunction "1_1") (pintype "passive"))
      (node (ref "U14") (pin "26") (pinfunction "IREF_26") (pintype "passive"))
    )
    (net (code "41") (name "Net-(U14-VCC)") (class "Default")
      (node (ref "C26") (pin "2") (pinfunction "2_2") (pintype "passive"))
      (node (ref "U14") (pin "28") (pinfunction "VCC_28") (pintype "passive"))
    )
    (net (code "42") (name "Net-(U14-VCOMH)") (class "Default")
      (node (ref "C27") (pin "2") (pinfunction "2_2") (pintype "passive"))
      (node (ref "U14") (pin "27") (pinfunction "VCOMH_27") (pintype "passive"))
    )
    (net (code "43") (name "unconnected-(CN1-S5-PadH2)") (class "Default")
      (node (ref "CN1") (pin "H2") (pinfunction "S5_H2") (pintype "passive"))
    )
    (net (code "44") (name "unconnected-(CN1-S6-PadH1)") (class "Default")
      (node (ref "CN1") (pin "H1") (pinfunction "S6_H1") (pintype "passive"))
    )
    (net (code "45") (name "unconnected-(CN1-SBU1-PadA8)") (class "Default")
      (node (ref "CN1") (pin "A8") (pinfunction "SBU1_A8") (pintype "passive+no_connect"))
    )
    (net (code "46") (name "unconnected-(CN1-SBU2-PadB8)") (class "Default")
      (node (ref "CN1") (pin "B8") (pinfunction "SBU2_B8") (pintype "passive+no_connect"))
    )
    (net (code "47") (name "unconnected-(U3B-NC-Pad1)") (class "Default")
      (node (ref "U3") (pin "1") (pinfunction "NC_1") (pintype "passive"))
    )
    (net (code "48") (name "unconnected-(U5B-NC-Pad1)") (class "Default")
      (node (ref "U5") (pin "1") (pinfunction "NC_1") (pintype "passive"))
    )
    (net (code "49") (name "unconnected-(U6B-NC-Pad1)") (class "Default")
      (node (ref "U6") (pin "1") (pinfunction "NC_1") (pintype "passive"))
    )
    (net (code "50") (name "unconnected-(U8B-NC-Pad1)") (class "Default")
      (node (ref "U8") (pin "1") (pinfunction "NC_1") (pintype "passive"))
    )
    (net (code "51") (name "unconnected-(U14-mech-Pad31)") (class "Default")
      (node (ref "U14") (pin "31") (pinfunction "mech_31") (pintype "passive"))
    )
    (net (code "52") (name "unconnected-(U15-CTS-Pad5)") (class "Default")
      (node (ref "U15") (pin "5") (pinfunction "CTS_5") (pintype "input+no_connect"))
    )
    (net (code "53") (name "unconnected-(U15-RTS-Pad4)") (class "Default")
      (node (ref "U15") (pin "4") (pinfunction "RTS_4") (pintype "input+no_connect"))
    )
    (net (code "54") (name "unconnected-(U15-Tnow-Pad6)") (class "Default")
      (node (ref "U15") (pin "6") (pinfunction "Tnow_6") (pintype "input+no_connect"))
    )
  )
)
